# AirTHD.net
KiCad netlist of a schematic drawn in Altium Designer
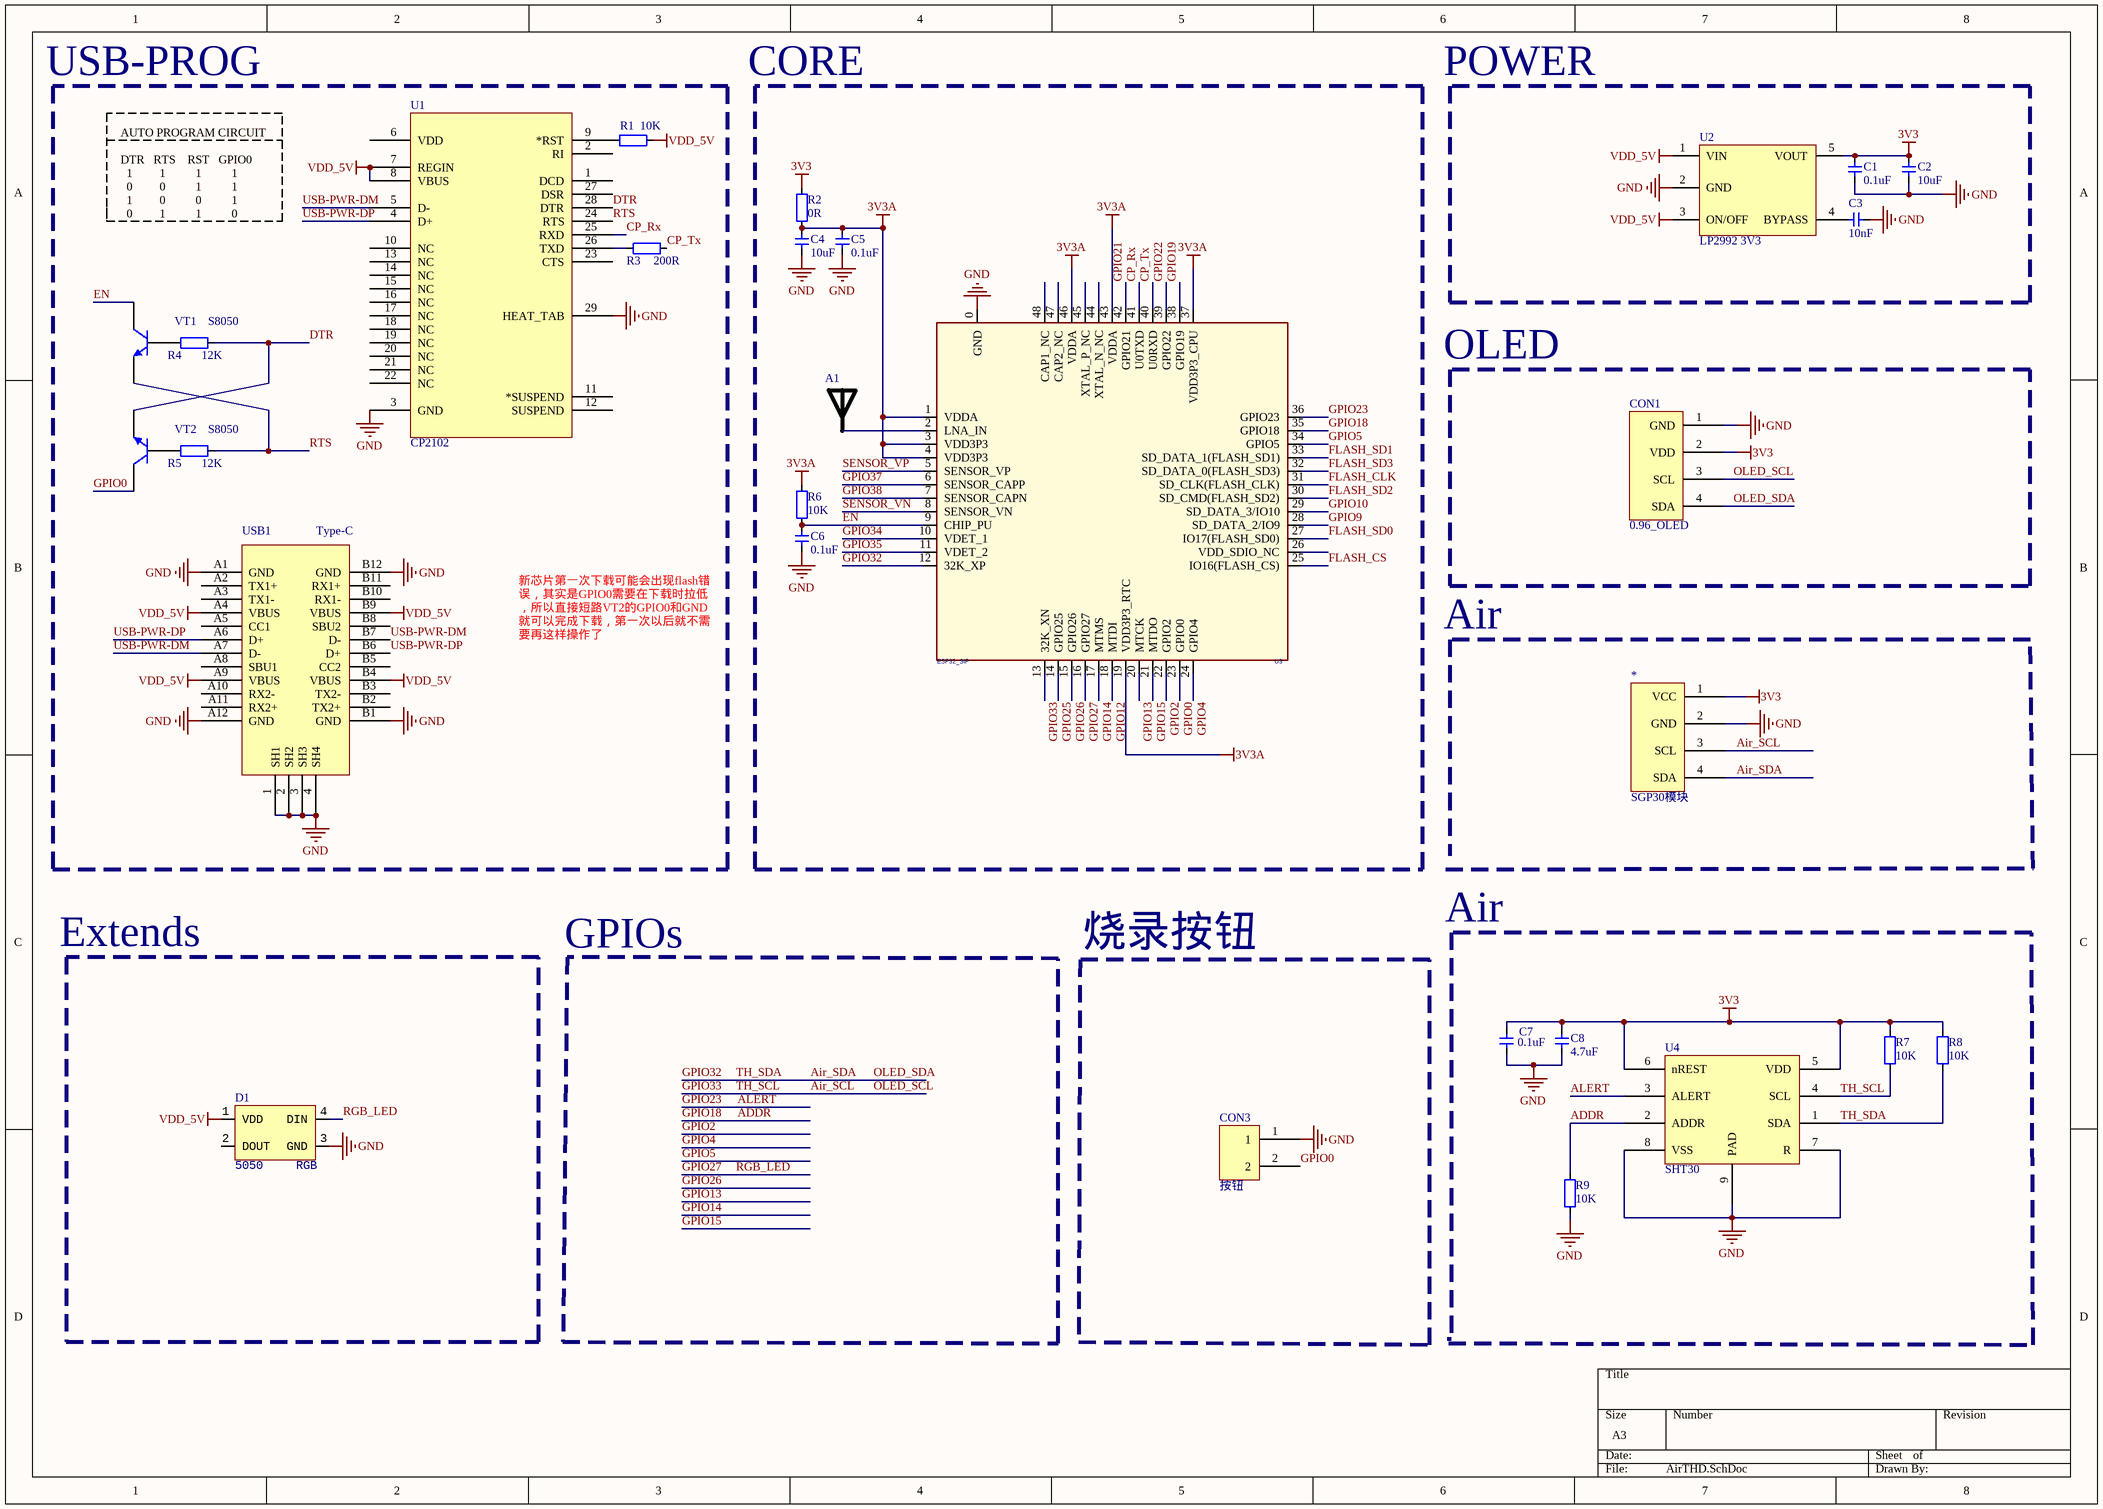
[diagram p0: AirTHD.SchDoc]

(export (version "E")
  (design (tool "Eeschema 10.0.6"))
  (components
    (comp (ref "*") (value "SGP30模块") (footprint "4Pin排针") (libsource (lib "Schlib1") (part "SGP30模块")))
    (comp (ref "A1")
      (value "RAINSUN")
      (footprint "ANT-Rainsun-AN5120")
      (libsource (lib "MyPcbLib") (part "ANT-Rainsun-AP5120"))
    )
    (comp (ref "C1")
      (value "0.1uF")
      (footprint "CAP_0402")
      (description "Capacitor")
      (libsource (lib "MyPcbLib") (part "电容-0402"))
    )
    (comp (ref "C2")
      (value "10uF")
      (footprint "CAP_0402")
      (description "Capacitor")
      (libsource (lib "MyPcbLib") (part "电容-0402"))
    )
    (comp (ref "C3")
      (value "10nF")
      (footprint "CAP_0402")
      (description "Capacitor")
      (libsource (lib "MyPcbLib") (part "电容-0402"))
    )
    (comp (ref "C4")
      (value "10uF")
      (footprint "CAP_0402")
      (description "Capacitor")
      (libsource (lib "MyPcbLib") (part "电容-0402"))
    )
    (comp (ref "C5")
      (value "0.1uF")
      (footprint "CAP_0402")
      (description "Capacitor")
      (libsource (lib "MyPcbLib") (part "电容-0402"))
    )
    (comp (ref "C6")
      (value "0.1uF")
      (footprint "CAP_0402")
      (description "Capacitor")
      (libsource (lib "MyPcbLib") (part "电容-0402"))
    )
    (comp (ref "C7")
      (value "0.1uF")
      (footprint "CAP_0402")
      (description "Capacitor")
      (libsource (lib "MainBoard") (part "电容-0402"))
    )
    (comp (ref "C8")
      (value "4.7uF")
      (footprint "CAP_0402")
      (description "Capacitor")
      (libsource (lib "MainBoard") (part "电容-0402"))
    )
    (comp (ref "CON1")
      (value "0.96_OLED")
      (footprint "4Pin排针")
      (libsource (lib "Schlib1") (part "0.96_OLED"))
    )
    (comp (ref "CON3") (value "按钮") (footprint "3*4贴片按钮") (libsource (lib "Schlib1") (part "按钮")))
    (comp (ref "D1")
      (value "RGB")
      (footprint "LED_5050_WS2812B")
      (description "LED")
      (fields (field (name "TYPE") "5050"))
      (libsource (lib "KitSprout") (part "LED_5050_WS2812B"))
    )
    (comp (ref "R1")
      (value "10K")
      (footprint "RES_0402")
      (description "Resistor")
      (libsource (lib "MyPcbLib") (part "电阻-0402"))
    )
    (comp (ref "R2")
      (value "0R")
      (footprint "RES_0402")
      (description "Resistor")
      (libsource (lib "") (part "电阻-0402_1"))
    )
    (comp (ref "R3")
      (value "200R")
      (footprint "RES_0402")
      (description "Resistor")
      (libsource (lib "MyPcbLib") (part "电阻-0402"))
    )
    (comp (ref "R4")
      (value "12K")
      (footprint "RES_0402")
      (description "Resistor")
      (libsource (lib "MyPcbLib") (part "电阻-0402"))
    )
    (comp (ref "R5")
      (value "12K")
      (footprint "RES_0402")
      (description "Resistor")
      (libsource (lib "MyPcbLib") (part "电阻-0402"))
    )
    (comp (ref "R6")
      (value "10K")
      (footprint "RES_0402")
      (description "Resistor")
      (libsource (lib "") (part "电阻-0402_1"))
    )
    (comp (ref "R7")
      (value "10K")
      (footprint "RES_0402")
      (description "Resistor")
      (libsource (lib "MainBoard") (part "电阻-0402"))
    )
    (comp (ref "R8")
      (value "10K")
      (footprint "RES_0402")
      (description "Resistor")
      (libsource (lib "MainBoard") (part "电阻-0402"))
    )
    (comp (ref "R9")
      (value "10K")
      (footprint "RES_0402")
      (description "Resistor")
      (libsource (lib "MainBoard") (part "电阻-0402"))
    )
    (comp (ref "U1")
      (value "CP2102")
      (footprint "QFN-28")
      (description "USB转TTL")
      (libsource (lib "mLib") (part "CP2102"))
    )
    (comp (ref "U2")
      (value "LP2992 3V3")
      (footprint "SOT23-5")
      (description "LDO")
      (libsource (lib "MyPcbLib") (part "LP2992"))
    )
    (comp (ref "U3")
      (value "ESP32_SIP")
      (footprint "QFN-48_7X7")
      (libsource (lib "MyPcbLib") (part "ESP32-PICO"))
    )
    (comp (ref "U4") (value "SHT30") (footprint "SHT30") (libsource (lib "Schlib1") (part "SHT30")))
    (comp (ref "USB1")
      (value "Type-C")
      (footprint "Type-C-TOP")
      (libsource (lib "MyPcbLib") (part "USB-Type-C-TOP"))
    )
    (comp (ref "VT1")
      (value "S8050")
      (footprint "SMT_TRIODE_NPN")
      (description "Surface mount NPN transistor, package SOT-23")
      (libsource (lib "MyPcbLib") (part "SMT_TRIODE_NPN"))
    )
    (comp (ref "VT2")
      (value "S8050")
      (footprint "SMT_TRIODE_NPN")
      (description "Surface mount NPN transistor, package SOT-23")
      (libsource (lib "MyPcbLib") (part "SMT_TRIODE_NPN"))
    )
  )
  (nets
    (net (code "1") (name "/ADDR") (class "Default")
      (node (ref "R9") (pin "2") (pinfunction "2_2") (pintype "passive"))
      (node (ref "U3") (pin "35") (pinfunction "GPIO18_35") (pintype "passive"))
      (node (ref "U4") (pin "2") (pinfunction "ADDR_2") (pintype "passive"))
    )
    (net (code "2") (name "/ALERT") (class "Default")
      (node (ref "U3") (pin "36") (pinfunction "GPIO23_36") (pintype "passive"))
      (node (ref "U4") (pin "3") (pinfunction "ALERT_3") (pintype "passive"))
    )
    (net (code "3") (name "/Air_SCL") (class "Default")
      (node (ref "*") (pin "3") (pinfunction "SCL_3") (pintype "passive"))
      (node (ref "CON1") (pin "3") (pinfunction "SCL_3") (pintype "passive"))
      (node (ref "R7") (pin "1") (pinfunction "1_1") (pintype "passive"))
      (node (ref "U3") (pin "13") (pinfunction "32K_XN_13") (pintype "passive"))
      (node (ref "U4") (pin "4") (pinfunction "SCL_4") (pintype "passive"))
    )
    (net (code "4") (name "/Air_SDA") (class "Default")
      (node (ref "*") (pin "4") (pinfunction "SDA_4") (pintype "passive"))
      (node (ref "CON1") (pin "4") (pinfunction "SDA_4") (pintype "passive"))
      (node (ref "R8") (pin "1") (pinfunction "1_1") (pintype "passive"))
      (node (ref "U3") (pin "12") (pinfunction "32K_XP_12") (pintype "passive"))
      (node (ref "U4") (pin "1") (pinfunction "SDA_1") (pintype "passive"))
    )
    (net (code "5") (name "/CP_Rx") (class "Default")
      (node (ref "U1") (pin "25") (pinfunction "RXD_25") (pintype "passive"))
      (node (ref "U3") (pin "41") (pinfunction "U0TXD_41") (pintype "power_in"))
    )
    (net (code "6") (name "/CP_Tx") (class "Default")
      (node (ref "R3") (pin "1") (pinfunction "1_1") (pintype "passive"))
      (node (ref "U3") (pin "40") (pinfunction "U0RXD_40") (pintype "power_in"))
    )
    (net (code "7") (name "/DTR") (class "Default")
      (node (ref "R4") (pin "1") (pinfunction "1_1") (pintype "passive"))
      (node (ref "U1") (pin "28") (pinfunction "DTR_28") (pintype "passive"))
      (node (ref "VT2") (pin "2") (pinfunction "E_2") (pintype "passive"))
    )
    (net (code "8") (name "/EN") (class "Default")
      (node (ref "C6") (pin "1") (pinfunction "1_1") (pintype "passive"))
      (node (ref "R6") (pin "2") (pinfunction "2_2") (pintype "passive"))
      (node (ref "U3") (pin "9") (pinfunction "CHIP_PU_9") (pintype "passive"))
      (node (ref "VT1") (pin "3") (pinfunction "C_3") (pintype "passive"))
    )
    (net (code "9") (name "/FLASH_CLK") (class "Default")
      (node (ref "U3") (pin "31") (pinfunction "SD_CLK(FLASH_CLK)_31") (pintype "passive"))
    )
    (net (code "10") (name "/FLASH_CS") (class "Default")
      (node (ref "U3") (pin "25") (pinfunction "IO16(FLASH_CS)_25") (pintype "passive"))
    )
    (net (code "11") (name "/FLASH_SD0") (class "Default")
      (node (ref "U3") (pin "27") (pinfunction "IO17(FLASH_SD0)_27") (pintype "passive"))
    )
    (net (code "12") (name "/FLASH_SD1") (class "Default")
      (node (ref "U3") (pin "33") (pinfunction "SD_DATA_1(FLASH_SD1)_33") (pintype "passive"))
    )
    (net (code "13") (name "/FLASH_SD2") (class "Default")
      (node (ref "U3") (pin "30") (pinfunction "SD_CMD(FLASH_SD2)_30") (pintype "passive"))
    )
    (net (code "14") (name "/FLASH_SD3") (class "Default")
      (node (ref "U3") (pin "32") (pinfunction "SD_DATA_0(FLASH_SD3)_32") (pintype "passive"))
    )
    (net (code "15") (name "/GPIO0") (class "Default")
      (node (ref "CON3") (pin "2") (pinfunction "2_2") (pintype "passive"))
      (node (ref "U3") (pin "23") (pinfunction "GPIO0_23") (pintype "passive"))
      (node (ref "VT2") (pin "3") (pinfunction "C_3") (pintype "passive"))
    )
    (net (code "16") (name "/GPIO2") (class "Default")
      (node (ref "U3") (pin "22") (pinfunction "GPIO2_22") (pintype "passive"))
    )
    (net (code "17") (name "/GPIO4") (class "Default")
      (node (ref "U3") (pin "24") (pinfunction "GPIO4_24") (pintype "passive"))
    )
    (net (code "18") (name "/GPIO5") (class "Default")
      (node (ref "U3") (pin "34") (pinfunction "GPIO5_34") (pintype "passive"))
    )
    (net (code "19") (name "/GPIO9") (class "Default")
      (node (ref "U3") (pin "28") (pinfunction "SD_DATA_2/IO9_28") (pintype "passive"))
    )
    (net (code "20") (name "/GPIO10") (class "Default")
      (node (ref "U3") (pin "29") (pinfunction "SD_DATA_3/IO10_29") (pintype "passive"))
    )
    (net (code "21") (name "/GPIO12") (class "Default")
      (node (ref "U3") (pin "18") (pinfunction "MTDI_18") (pintype "passive"))
    )
    (net (code "22") (name "/GPIO13") (class "Default")
      (node (ref "U3") (pin "20") (pinfunction "MTCK_20") (pintype "passive"))
    )
    (net (code "23") (name "/GPIO14") (class "Default")
      (node (ref "U3") (pin "17") (pinfunction "MTMS_17") (pintype "passive"))
    )
    (net (code "24") (name "/GPIO15") (class "Default")
      (node (ref "U3") (pin "21") (pinfunction "MTDO_21") (pintype "passive"))
    )
    (net (code "25") (name "/GPIO19") (class "Default")
      (node (ref "U3") (pin "38") (pinfunction "GPIO19_38") (pintype "passive"))
    )
    (net (code "26") (name "/GPIO21") (class "Default")
      (node (ref "U3") (pin "42") (pinfunction "GPIO21_42") (pintype "passive"))
    )
    (net (code "27") (name "/GPIO22") (class "Default")
      (node (ref "U3") (pin "39") (pinfunction "GPIO22_39") (pintype "passive"))
    )
    (net (code "28") (name "/GPIO25") (class "Default")
      (node (ref "U3") (pin "14") (pinfunction "GPIO25_14") (pintype "passive"))
    )
    (net (code "29") (name "/GPIO26") (class "Default")
      (node (ref "U3") (pin "15") (pinfunction "GPIO26_15") (pintype "passive"))
    )
    (net (code "30") (name "/GPIO27") (class "Default")
      (node (ref "D1") (pin "4") (pinfunction "DIN_4") (pintype "passive"))
      (node (ref "U3") (pin "16") (pinfunction "GPIO27_16") (pintype "passive"))
    )
    (net (code "31") (name "/GPIO34") (class "Default")
      (node (ref "U3") (pin "10") (pinfunction "VDET_1_10") (pintype "passive"))
    )
    (net (code "32") (name "/GPIO35") (class "Default")
      (node (ref "U3") (pin "11") (pinfunction "VDET_2_11") (pintype "passive"))
    )
    (net (code "33") (name "/GPIO37") (class "Default")
      (node (ref "U3") (pin "6") (pinfunction "SENSOR_CAPP_6") (pintype "passive"))
    )
    (net (code "34") (name "/GPIO38") (class "Default")
      (node (ref "U3") (pin "7") (pinfunction "SENSOR_CAPN_7") (pintype "passive"))
    )
    (net (code "35") (name "/RTS") (class "Default")
      (node (ref "R5") (pin "1") (pinfunction "1_1") (pintype "passive"))
      (node (ref "U1") (pin "24") (pinfunction "RTS_24") (pintype "passive"))
      (node (ref "VT1") (pin "2") (pinfunction "E_2") (pintype "passive"))
    )
    (net (code "36") (name "/SENSOR_VN") (class "Default")
      (node (ref "U3") (pin "8") (pinfunction "SENSOR_VN_8") (pintype "passive"))
    )
    (net (code "37") (name "/SENSOR_VP") (class "Default")
      (node (ref "U3") (pin "5") (pinfunction "SENSOR_VP_5") (pintype "passive"))
    )
    (net (code "38") (name "/USB-PWR-DM") (class "Default")
      (node (ref "U1") (pin "5") (pinfunction "D-_5") (pintype "passive"))
      (node (ref "USB1") (pin "A7") (pinfunction "D-_A7") (pintype "passive"))
      (node (ref "USB1") (pin "B7") (pinfunction "D-_B7") (pintype "passive"))
    )
    (net (code "39") (name "/USB-PWR-DP") (class "Default")
      (node (ref "U1") (pin "4") (pinfunction "D+_4") (pintype "passive"))
      (node (ref "USB1") (pin "A6") (pinfunction "D+_A6") (pintype "passive"))
      (node (ref "USB1") (pin "B6") (pinfunction "D+_B6") (pintype "passive"))
    )
    (net (code "40") (name "3V3") (class "Default")
      (node (ref "*") (pin "1") (pinfunction "VCC_1") (pintype "passive"))
      (node (ref "C1") (pin "2") (pinfunction "2_2") (pintype "passive"))
      (node (ref "C2") (pin "2") (pinfunction "2_2") (pintype "passive"))
      (node (ref "C7") (pin "2") (pinfunction "2_2") (pintype "passive"))
      (node (ref "C8") (pin "2") (pinfunction "2_2") (pintype "passive"))
      (node (ref "CON1") (pin "2") (pinfunction "VDD_2") (pintype "passive"))
      (node (ref "R2") (pin "1") (pinfunction "1_1") (pintype "passive"))
      (node (ref "R7") (pin "2") (pinfunction "2_2") (pintype "passive"))
      (node (ref "R8") (pin "2") (pinfunction "2_2") (pintype "passive"))
      (node (ref "U2") (pin "5") (pinfunction "VOUT_5") (pintype "passive"))
      (node (ref "U4") (pin "5") (pinfunction "VDD_5") (pintype "passive"))
      (node (ref "U4") (pin "6") (pinfunction "nREST_6") (pintype "passive"))
    )
    (net (code "41") (name "3V3A") (class "Default")
      (node (ref "C4") (pin "2") (pinfunction "2_2") (pintype "passive"))
      (node (ref "C5") (pin "2") (pinfunction "2_2") (pintype "passive"))
      (node (ref "R2") (pin "2") (pinfunction "2_2") (pintype "passive"))
      (node (ref "R6") (pin "1") (pinfunction "1_1") (pintype "passive"))
      (node (ref "U3") (pin "1") (pinfunction "VDDA_1") (pintype "power_in"))
      (node (ref "U3") (pin "19") (pinfunction "VDD3P3_RTC_19") (pintype "power_in"))
      (node (ref "U3") (pin "3") (pinfunction "VDD3P3_3") (pintype "power_in"))
      (node (ref "U3") (pin "37") (pinfunction "VDD3P3_CPU_37") (pintype "power_in"))
      (node (ref "U3") (pin "4") (pinfunction "VDD3P3_4") (pintype "power_in"))
      (node (ref "U3") (pin "43") (pinfunction "VDDA_43") (pintype "power_in"))
      (node (ref "U3") (pin "46") (pinfunction "VDDA_46") (pintype "power_in"))
    )
    (net (code "42") (name "GND") (class "Default")
      (node (ref "*") (pin "2") (pinfunction "GND_2") (pintype "passive"))
      (node (ref "C1") (pin "1") (pinfunction "1_1") (pintype "passive"))
      (node (ref "C2") (pin "1") (pinfunction "1_1") (pintype "passive"))
      (node (ref "C3") (pin "1") (pinfunction "1_1") (pintype "passive"))
      (node (ref "C4") (pin "1") (pinfunction "1_1") (pintype "passive"))
      (node (ref "C5") (pin "1") (pinfunction "1_1") (pintype "passive"))
      (node (ref "C6") (pin "2") (pinfunction "2_2") (pintype "passive"))
      (node (ref "C7") (pin "1") (pinfunction "1_1") (pintype "passive"))
      (node (ref "C8") (pin "1") (pinfunction "1_1") (pintype "passive"))
      (node (ref "CON1") (pin "1") (pinfunction "GND_1") (pintype "passive"))
      (node (ref "CON3") (pin "1") (pinfunction "1_1") (pintype "passive"))
      (node (ref "D1") (pin "3") (pinfunction "GND_3") (pintype "passive"))
      (node (ref "R9") (pin "1") (pinfunction "1_1") (pintype "passive"))
      (node (ref "U1") (pin "29") (pinfunction "HEAT_TAB_29") (pintype "passive"))
      (node (ref "U1") (pin "3") (pinfunction "GND_3") (pintype "passive"))
      (node (ref "U2") (pin "2") (pinfunction "GND_2") (pintype "passive"))
      (node (ref "U3") (pin "0") (pinfunction "GND_0") (pintype "power_in"))
      (node (ref "U4") (pin "7") (pinfunction "R_7") (pintype "passive"))
      (node (ref "U4") (pin "8") (pinfunction "VSS_8") (pintype "passive"))
      (node (ref "U4") (pin "9") (pinfunction "PAD_9") (pintype "passive"))
      (node (ref "USB1") (pin "1") (pinfunction "SH1_1") (pintype "passive"))
      (node (ref "USB1") (pin "2") (pinfunction "SH2_2") (pintype "passive"))
      (node (ref "USB1") (pin "3") (pinfunction "SH3_3") (pintype "passive"))
      (node (ref "USB1") (pin "4") (pinfunction "SH4_4") (pintype "passive"))
      (node (ref "USB1") (pin "A1") (pinfunction "GND_A1") (pintype "passive"))
      (node (ref "USB1") (pin "A12") (pinfunction "GND_A12") (pintype "passive"))
      (node (ref "USB1") (pin "B1") (pinfunction "GND_B1") (pintype "passive"))
      (node (ref "USB1") (pin "B12") (pinfunction "GND_B12") (pintype "passive"))
    )
    (net (code "43") (name "Net-(U1-*RST)") (class "Default")
      (node (ref "R1") (pin "2") (pinfunction "2_2") (pintype "passive"))
      (node (ref "U1") (pin "9") (pinfunction "*RST_9") (pintype "passive"))
    )
    (net (code "44") (name "Net-(U1-TXD)") (class "Default")
      (node (ref "R3") (pin "2") (pinfunction "2_2") (pintype "passive"))
      (node (ref "U1") (pin "26") (pinfunction "TXD_26") (pintype "passive"))
    )
    (net (code "45") (name "Net-(U2-BYPASS)") (class "Default")
      (node (ref "C3") (pin "2") (pinfunction "2_2") (pintype "passive"))
      (node (ref "U2") (pin "4") (pinfunction "BYPASS_4") (pintype "passive"))
    )
    (net (code "46") (name "Net-(U3-LNA_IN)") (class "Default")
      (node (ref "A1") (pin "1") (pinfunction "1_1") (pintype "passive"))
      (node (ref "U3") (pin "2") (pinfunction "LNA_IN_2") (pintype "passive"))
    )
    (net (code "47") (name "Net-(VT1-B)") (class "Default")
      (node (ref "R4") (pin "2") (pinfunction "2_2") (pintype "passive"))
      (node (ref "VT1") (pin "1") (pinfunction "B_1") (pintype "passive"))
    )
    (net (code "48") (name "Net-(VT2-B)") (class "Default")
      (node (ref "R5") (pin "2") (pinfunction "2_2") (pintype "passive"))
      (node (ref "VT2") (pin "1") (pinfunction "B_1") (pintype "passive"))
    )
    (net (code "49") (name "VDD_5V") (class "Default")
      (node (ref "D1") (pin "1") (pinfunction "VDD_1") (pintype "passive"))
      (node (ref "R1") (pin "1") (pinfunction "1_1") (pintype "passive"))
      (node (ref "U1") (pin "7") (pinfunction "REGIN_7") (pintype "passive"))
      (node (ref "U1") (pin "8") (pinfunction "VBUS_8") (pintype "passive"))
      (node (ref "U2") (pin "1") (pinfunction "VIN_1") (pintype "passive"))
      (node (ref "U2") (pin "3") (pinfunction "ON/OFF_3") (pintype "passive"))
      (node (ref "USB1") (pin "A4") (pinfunction "VBUS_A4") (pintype "passive"))
      (node (ref "USB1") (pin "A9") (pinfunction "VBUS_A9") (pintype "passive"))
      (node (ref "USB1") (pin "B4") (pinfunction "VBUS_B4") (pintype "passive"))
      (node (ref "USB1") (pin "B9") (pinfunction "VBUS_B9") (pintype "passive"))
    )
    (net (code "50") (name "unconnected-(D1-DOUT-Pad2)") (class "Default")
      (node (ref "D1") (pin "2") (pinfunction "DOUT_2") (pintype "passive"))
    )
    (net (code "51") (name "unconnected-(U1-*SUSPEND-Pad11)") (class "Default")
      (node (ref "U1") (pin "11") (pinfunction "*SUSPEND_11") (pintype "passive"))
    )
    (net (code "52") (name "unconnected-(U1-CTS-Pad23)") (class "Default")
      (node (ref "U1") (pin "23") (pinfunction "CTS_23") (pintype "passive"))
    )
    (net (code "53") (name "unconnected-(U1-DCD-Pad1)") (class "Default")
      (node (ref "U1") (pin "1") (pinfunction "DCD_1") (pintype "passive"))
    )
    (net (code "54") (name "unconnected-(U1-DSR-Pad27)") (class "Default")
      (node (ref "U1") (pin "27") (pinfunction "DSR_27") (pintype "passive"))
    )
    (net (code "55") (name "unconnected-(U1-NC-Pad10)") (class "Default")
      (node (ref "U1") (pin "10") (pinfunction "NC_10") (pintype "passive"))
    )
    (net (code "56") (name "unconnected-(U1-NC-Pad13)") (class "Default")
      (node (ref "U1") (pin "13") (pinfunction "NC_13") (pintype "passive"))
    )
    (net (code "57") (name "unconnected-(U1-NC-Pad14)") (class "Default")
      (node (ref "U1") (pin "14") (pinfunction "NC_14") (pintype "passive"))
    )
    (net (code "58") (name "unconnected-(U1-NC-Pad15)") (class "Default")
      (node (ref "U1") (pin "15") (pinfunction "NC_15") (pintype "passive"))
    )
    (net (code "59") (name "unconnected-(U1-NC-Pad16)") (class "Default")
      (node (ref "U1") (pin "16") (pinfunction "NC_16") (pintype "passive"))
    )
    (net (code "60") (name "unconnected-(U1-NC-Pad17)") (class "Default")
      (node (ref "U1") (pin "17") (pinfunction "NC_17") (pintype "passive"))
    )
    (net (code "61") (name "unconnected-(U1-NC-Pad18)") (class "Default")
      (node (ref "U1") (pin "18") (pinfunction "NC_18") (pintype "passive"))
    )
    (net (code "62") (name "unconnected-(U1-NC-Pad19)") (class "Default")
      (node (ref "U1") (pin "19") (pinfunction "NC_19") (pintype "passive"))
    )
    (net (code "63") (name "unconnected-(U1-NC-Pad20)") (class "Default")
      (node (ref "U1") (pin "20") (pinfunction "NC_20") (pintype "passive"))
    )
    (net (code "64") (name "unconnected-(U1-NC-Pad21)") (class "Default")
      (node (ref "U1") (pin "21") (pinfunction "NC_21") (pintype "passive"))
    )
    (net (code "65") (name "unconnected-(U1-NC-Pad22)") (class "Default")
      (node (ref "U1") (pin "22") (pinfunction "NC_22") (pintype "passive"))
    )
    (net (code "66") (name "unconnected-(U1-RI-Pad2)") (class "Default")
      (node (ref "U1") (pin "2") (pinfunction "RI_2") (pintype "passive"))
    )
    (net (code "67") (name "unconnected-(U1-SUSPEND-Pad12)") (class "Default")
      (node (ref "U1") (pin "12") (pinfunction "SUSPEND_12") (pintype "passive"))
    )
    (net (code "68") (name "unconnected-(U1-VDD-Pad6)") (class "Default")
      (node (ref "U1") (pin "6") (pinfunction "VDD_6") (pintype "passive"))
    )
    (net (code "69") (name "unconnected-(U3-CAP1_NC-Pad48)") (class "Default")
      (node (ref "U3") (pin "48") (pinfunction "CAP1_NC_48") (pintype "passive"))
    )
    (net (code "70") (name "unconnected-(U3-CAP2_NC-Pad47)") (class "Default")
      (node (ref "U3") (pin "47") (pinfunction "CAP2_NC_47") (pintype "passive"))
    )
    (net (code "71") (name "unconnected-(U3-VDD_SDIO_NC-Pad26)") (class "Default")
      (node (ref "U3") (pin "26") (pinfunction "VDD_SDIO_NC_26") (pintype "passive"))
    )
    (net (code "72") (name "unconnected-(U3-XTAL_N_NC-Pad44)") (class "Default")
      (node (ref "U3") (pin "44") (pinfunction "XTAL_N_NC_44") (pintype "passive"))
    )
    (net (code "73") (name "unconnected-(U3-XTAL_P_NC-Pad45)") (class "Default")
      (node (ref "U3") (pin "45") (pinfunction "XTAL_P_NC_45") (pintype "passive"))
    )
    (net (code "74") (name "unconnected-(USB1-CC1-PadA5)") (class "Default")
      (node (ref "USB1") (pin "A5") (pinfunction "CC1_A5") (pintype "passive"))
    )
    (net (code "75") (name "unconnected-(USB1-CC2-PadB5)") (class "Default")
      (node (ref "USB1") (pin "B5") (pinfunction "CC2_B5") (pintype "passive"))
    )
    (net (code "76") (name "unconnected-(USB1-RX1+-PadB11)") (class "Default")
      (node (ref "USB1") (pin "B11") (pinfunction "RX1+_B11") (pintype "passive"))
    )
    (net (code "77") (name "unconnected-(USB1-RX1--PadB10)") (class "Default")
      (node (ref "USB1") (pin "B10") (pinfunction "RX1-_B10") (pintype "passive"))
    )
    (net (code "78") (name "unconnected-(USB1-RX2+-PadA11)") (class "Default")
      (node (ref "USB1") (pin "A11") (pinfunction "RX2+_A11") (pintype "passive"))
    )
    (net (code "79") (name "unconnected-(USB1-RX2--PadA10)") (class "Default")
      (node (ref "USB1") (pin "A10") (pinfunction "RX2-_A10") (pintype "passive"))
    )
    (net (code "80") (name "unconnected-(USB1-SBU1-PadA8)") (class "Default")
      (node (ref "USB1") (pin "A8") (pinfunction "SBU1_A8") (pintype "passive"))
    )
    (net (code "81") (name "unconnected-(USB1-SBU2-PadB8)") (class "Default")
      (node (ref "USB1") (pin "B8") (pinfunction "SBU2_B8") (pintype "passive"))
    )
    (net (code "82") (name "unconnected-(USB1-TX1+-PadA2)") (class "Default")
      (node (ref "USB1") (pin "A2") (pinfunction "TX1+_A2") (pintype "passive"))
    )
    (net (code "83") (name "unconnected-(USB1-TX1--PadA3)") (class "Default")
      (node (ref "USB1") (pin "A3") (pinfunction "TX1-_A3") (pintype "passive"))
    )
    (net (code "84") (name "unconnected-(USB1-TX2+-PadB2)") (class "Default")
      (node (ref "USB1") (pin "B2") (pinfunction "TX2+_B2") (pintype "passive"))
    )
    (net (code "85") (name "unconnected-(USB1-TX2--PadB3)") (class "Default")
      (node (ref "USB1") (pin "B3") (pinfunction "TX2-_B3") (pintype "passive"))
    )
  )
)
